# OpAmpSCH.net
KiCad netlist of a schematic drawn in Altium Designer
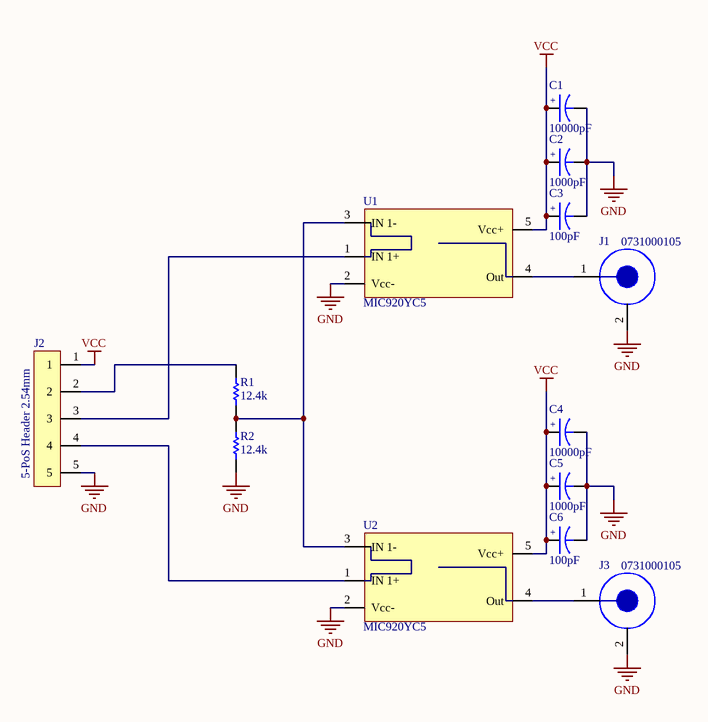
[diagram p0: OpAmpSCH.SchDoc]

(export (version "E")
  (design (tool "Eeschema 10.0.6"))
  (components
    (comp (ref "C1")
      (value "10000pF")
      (footprint "0603C")
      (description "Cap Poly")
      (libsource (lib "GENERIC_LIB") (part "CPoly"))
    )
    (comp (ref "C2")
      (value "1000pF")
      (footprint "0603C")
      (description "Cap Poly")
      (libsource (lib "GENERIC_LIB") (part "CPoly"))
    )
    (comp (ref "C3")
      (value "100pF")
      (footprint "0603C")
      (description "Cap Poly")
      (libsource (lib "GENERIC_LIB") (part "CPoly"))
    )
    (comp (ref "C4")
      (value "10000pF")
      (footprint "0603C")
      (description "Cap Poly")
      (libsource (lib "GENERIC_LIB") (part "CPoly"))
    )
    (comp (ref "C5")
      (value "1000pF")
      (footprint "0603C")
      (description "Cap Poly")
      (libsource (lib "GENERIC_LIB") (part "CPoly"))
    )
    (comp (ref "C6")
      (value "100pF")
      (footprint "0603C")
      (description "Cap Poly")
      (libsource (lib "GENERIC_LIB") (part "CPoly"))
    )
    (comp (ref "J1")
      (value "0731000105")
      (footprint "0731000105")
      (description "BNC Connector Jack, Female Socket 50Ohm Through Hole, Right Angle Solder")
      (libsource (lib "CON_LIB") (part "0731000105"))
    )
    (comp (ref "J2")
      (value "5-PoS Header 2.54mm")
      (footprint "2.54mm Pitch Header")
      (libsource (lib "CON_LIB") (part "5-PoS Header 2.54mm"))
    )
    (comp (ref "J3")
      (value "0731000105")
      (footprint "0731000105")
      (description "BNC Connector Jack, Female Socket 50Ohm Through Hole, Right Angle Solder")
      (libsource (lib "CON_LIB") (part "0731000105"))
    )
    (comp (ref "R1")
      (value "12.4k")
      (footprint "0603C")
      (description "Resistor")
      (fields (field (name "TOLERANCE") "5%"))
      (libsource (lib "GENERIC_LIB") (part "R"))
    )
    (comp (ref "R2")
      (value "12.4k")
      (footprint "0603C")
      (description "Resistor")
      (fields (field (name "TOLERANCE") "5%"))
      (libsource (lib "GENERIC_LIB") (part "R"))
    )
    (comp (ref "U1")
      (value "MIC920YC5")
      (footprint "MIC920")
      (description "General Purpose Amplifier 1 Circuit SC-70-5")
      (libsource (lib "ANALOG_LIB") (part "MIC920YC5-TR"))
    )
    (comp (ref "U2")
      (value "MIC920YC5")
      (footprint "MIC920")
      (description "General Purpose Amplifier 1 Circuit SC-70-5")
      (libsource (lib "ANALOG_LIB") (part "MIC920YC5-TR"))
    )
  )
  (nets
    (net (code "1") (name "GND") (class "Default")
      (node (ref "C1") (pin "2") (pinfunction "2_2") (pintype "passive"))
      (node (ref "C2") (pin "2") (pinfunction "2_2") (pintype "passive"))
      (node (ref "C3") (pin "2") (pinfunction "2_2") (pintype "passive"))
      (node (ref "C4") (pin "2") (pinfunction "2_2") (pintype "passive"))
      (node (ref "C5") (pin "2") (pinfunction "2_2") (pintype "passive"))
      (node (ref "C6") (pin "2") (pinfunction "2_2") (pintype "passive"))
      (node (ref "J1") (pin "2") (pinfunction "2_2") (pintype "passive"))
      (node (ref "J2") (pin "5") (pinfunction "5_5") (pintype "passive"))
      (node (ref "J3") (pin "2") (pinfunction "2_2") (pintype "passive"))
      (node (ref "R2") (pin "1") (pinfunction "1_1") (pintype "passive"))
      (node (ref "U1") (pin "2") (pinfunction "Vcc-_2") (pintype "passive"))
      (node (ref "U2") (pin "2") (pinfunction "Vcc-_2") (pintype "passive"))
    )
    (net (code "2") (name "Net-(J2-Pad2)") (class "Default")
      (node (ref "J2") (pin "2") (pinfunction "2_2") (pintype "passive"))
      (node (ref "R1") (pin "2") (pinfunction "2_2") (pintype "passive"))
    )
    (net (code "3") (name "Net-(U1-IN_1+)") (class "Default")
      (node (ref "J2") (pin "3") (pinfunction "3_3") (pintype "passive"))
      (node (ref "U1") (pin "1") (pinfunction "IN_1+_1") (pintype "passive"))
    )
    (net (code "4") (name "Net-(U1-IN_1-)") (class "Default")
      (node (ref "R1") (pin "1") (pinfunction "1_1") (pintype "passive"))
      (node (ref "R2") (pin "2") (pinfunction "2_2") (pintype "passive"))
      (node (ref "U1") (pin "3") (pinfunction "IN_1-_3") (pintype "passive"))
      (node (ref "U2") (pin "3") (pinfunction "IN_1-_3") (pintype "passive"))
    )
    (net (code "5") (name "Net-(U1-Out)") (class "Default")
      (node (ref "J1") (pin "1") (pinfunction "1_1") (pintype "passive"))
      (node (ref "U1") (pin "4") (pinfunction "Out_4") (pintype "passive"))
    )
    (net (code "6") (name "Net-(U2-IN_1+)") (class "Default")
      (node (ref "J2") (pin "4") (pinfunction "4_4") (pintype "passive"))
      (node (ref "U2") (pin "1") (pinfunction "IN_1+_1") (pintype "passive"))
    )
    (net (code "7") (name "Net-(U2-Out)") (class "Default")
      (node (ref "J3") (pin "1") (pinfunction "1_1") (pintype "passive"))
      (node (ref "U2") (pin "4") (pinfunction "Out_4") (pintype "passive"))
    )
    (net (code "8") (name "VCC") (class "Default")
      (node (ref "C1") (pin "1") (pinfunction "1_1") (pintype "passive"))
      (node (ref "C2") (pin "1") (pinfunction "1_1") (pintype "passive"))
      (node (ref "C3") (pin "1") (pinfunction "1_1") (pintype "passive"))
      (node (ref "C4") (pin "1") (pinfunction "1_1") (pintype "passive"))
      (node (ref "C5") (pin "1") (pinfunction "1_1") (pintype "passive"))
      (node (ref "C6") (pin "1") (pinfunction "1_1") (pintype "passive"))
      (node (ref "J2") (pin "1") (pinfunction "1_1") (pintype "passive"))
      (node (ref "U1") (pin "5") (pinfunction "Vcc+_5") (pintype "passive"))
      (node (ref "U2") (pin "5") (pinfunction "Vcc+_5") (pintype "passive"))
    )
  )
)
